# IT01.net
KiCad netlist of a schematic drawn in EAGLE
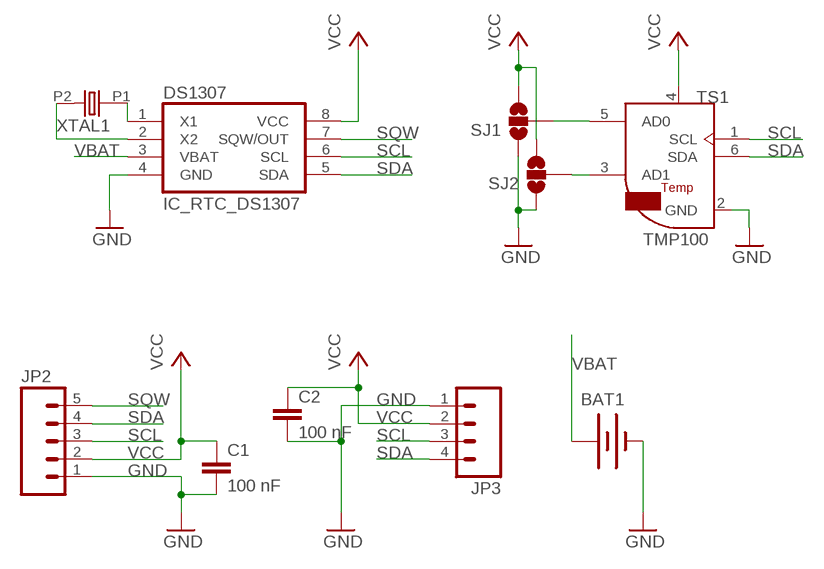
[diagram p0: schematic, sheet 1]

(export (version "E")
  (design (tool "Eeschema 10.0.6"))
  (components
    (comp (ref "BAT1")
      (value "BATTERY12MM")
      (footprint "eagle-import:BATTCON_12MM")
      (libsource (lib "eagle-import") (part "BATTERY12MM"))
    )
    (comp (ref "C1")
      (value "100 nF")
      (footprint "eagle-import:C0805")
      (libsource (lib "eagle-import") (part "C-EUC0805"))
    )
    (comp (ref "C2")
      (value "100 nF")
      (footprint "eagle-import:C0805")
      (libsource (lib "eagle-import") (part "C-EUC0805"))
    )
    (comp (ref "DS1307")
      (value "IC_RTC_DS1307")
      (footprint "eagle-import:SO-8")
      (libsource (lib "eagle-import") (part "IC_RTC_DS1307"))
    )
    (comp (ref "JP2")
      (value "M05PTH")
      (footprint "eagle-import:1X05")
      (libsource (lib "eagle-import") (part "M05PTH"))
    )
    (comp (ref "JP3")
      (value "M04PTH")
      (footprint "eagle-import:1X04")
      (libsource (lib "eagle-import") (part "M04PTH"))
    )
    (comp (ref "SJ1")
      (value "SOLDERJUMPER_2WAY-OLDT")
      (footprint "eagle-import:SJ_2")
      (libsource (lib "eagle-import") (part "SOLDERJUMPER_2WAY-OLDT"))
    )
    (comp (ref "SJ2")
      (value "SOLDERJUMPER_2WAY-OLDT")
      (footprint "eagle-import:SJ_2")
      (libsource (lib "eagle-import") (part "SOLDERJUMPER_2WAY-OLDT"))
    )
    (comp (ref "TS1")
      (value "TMP100")
      (footprint "eagle-import:SOT23-6")
      (libsource (lib "eagle-import") (part "TMP100"))
    )
    (comp (ref "XTAL1")
      (value "OSC-XTAL-TC-38")
      (footprint "eagle-import:TC-38")
      (libsource (lib "eagle-import") (part "OSC-XTAL-TC-38"))
    )
  )
  (nets
    (net (code "1") (name "/SCL") (class "Default")
      (node (ref "DS1307") (pin "6") (pinfunction "SCL_6") (pintype "bidirectional"))
      (node (ref "JP2") (pin "3") (pinfunction "3_3") (pintype "passive"))
      (node (ref "JP3") (pin "3") (pinfunction "3_3") (pintype "passive"))
      (node (ref "TS1") (pin "1") (pinfunction "SCL_1") (pintype "bidirectional"))
    )
    (net (code "2") (name "/SDA") (class "Default")
      (node (ref "DS1307") (pin "5") (pinfunction "SDA_5") (pintype "bidirectional"))
      (node (ref "JP2") (pin "4") (pinfunction "4_4") (pintype "passive"))
      (node (ref "JP3") (pin "4") (pinfunction "4_4") (pintype "passive"))
      (node (ref "TS1") (pin "6") (pinfunction "SDA_6") (pintype "bidirectional"))
    )
    (net (code "3") (name "/SQW") (class "Default")
      (node (ref "DS1307") (pin "7") (pinfunction "SQW/OUT_7") (pintype "bidirectional"))
      (node (ref "JP2") (pin "5") (pinfunction "5_5") (pintype "passive"))
    )
    (net (code "4") (name "/VBAT") (class "Default")
      (node (ref "BAT1") (pin "PWR@1") (pinfunction "+_PWR@1") (pintype "power_in"))
      (node (ref "DS1307") (pin "3") (pinfunction "VBAT_3") (pintype "bidirectional"))
    )
    (net (code "5") (name "GND") (class "Default")
      (node (ref "BAT1") (pin "GND") (pinfunction "-_GND") (pintype "power_in"))
      (node (ref "C1") (pin "2") (pinfunction "2_2") (pintype "passive"))
      (node (ref "C2") (pin "2") (pinfunction "2_2") (pintype "passive"))
      (node (ref "DS1307") (pin "4") (pinfunction "GND_4") (pintype "bidirectional"))
      (node (ref "JP2") (pin "1") (pinfunction "1_1") (pintype "passive"))
      (node (ref "JP3") (pin "1") (pinfunction "1_1") (pintype "passive"))
      (node (ref "SJ1") (pin "1") (pinfunction "1_1") (pintype "passive"))
      (node (ref "SJ2") (pin "1") (pinfunction "1_1") (pintype "passive"))
      (node (ref "TS1") (pin "2") (pinfunction "GND_2") (pintype "power_in"))
    )
    (net (code "6") (name "Net-(DS1307-X1)") (class "Default")
      (node (ref "DS1307") (pin "1") (pinfunction "X1_1") (pintype "bidirectional"))
      (node (ref "XTAL1") (pin "P1") (pinfunction "1_P1") (pintype "passive"))
    )
    (net (code "7") (name "Net-(DS1307-X2)") (class "Default")
      (node (ref "DS1307") (pin "2") (pinfunction "X2_2") (pintype "bidirectional"))
      (node (ref "XTAL1") (pin "P2") (pinfunction "2_P2") (pintype "passive"))
    )
    (net (code "8") (name "Net-(TS1-AD0)") (class "Default")
      (node (ref "SJ1") (pin "2") (pinfunction "2_2") (pintype "passive"))
      (node (ref "TS1") (pin "5") (pinfunction "AD0_5") (pintype "input"))
    )
    (net (code "9") (name "Net-(TS1-AD1)") (class "Default")
      (node (ref "SJ2") (pin "2") (pinfunction "2_2") (pintype "passive"))
      (node (ref "TS1") (pin "3") (pinfunction "AD1_3") (pintype "input"))
    )
    (net (code "10") (name "VCC") (class "Default")
      (node (ref "C1") (pin "1") (pinfunction "1_1") (pintype "passive"))
      (node (ref "C2") (pin "1") (pinfunction "1_1") (pintype "passive"))
      (node (ref "DS1307") (pin "8") (pinfunction "VCC_8") (pintype "bidirectional"))
      (node (ref "JP2") (pin "2") (pinfunction "2_2") (pintype "passive"))
      (node (ref "JP3") (pin "2") (pinfunction "2_2") (pintype "passive"))
      (node (ref "SJ1") (pin "3") (pinfunction "3_3") (pintype "passive"))
      (node (ref "SJ2") (pin "3") (pinfunction "3_3") (pintype "passive"))
      (node (ref "TS1") (pin "4") (pinfunction "UCC_4") (pintype "power_in"))
    )
  )
)
